# Sensors.net
KiCad netlist of a schematic drawn in Altium Designer
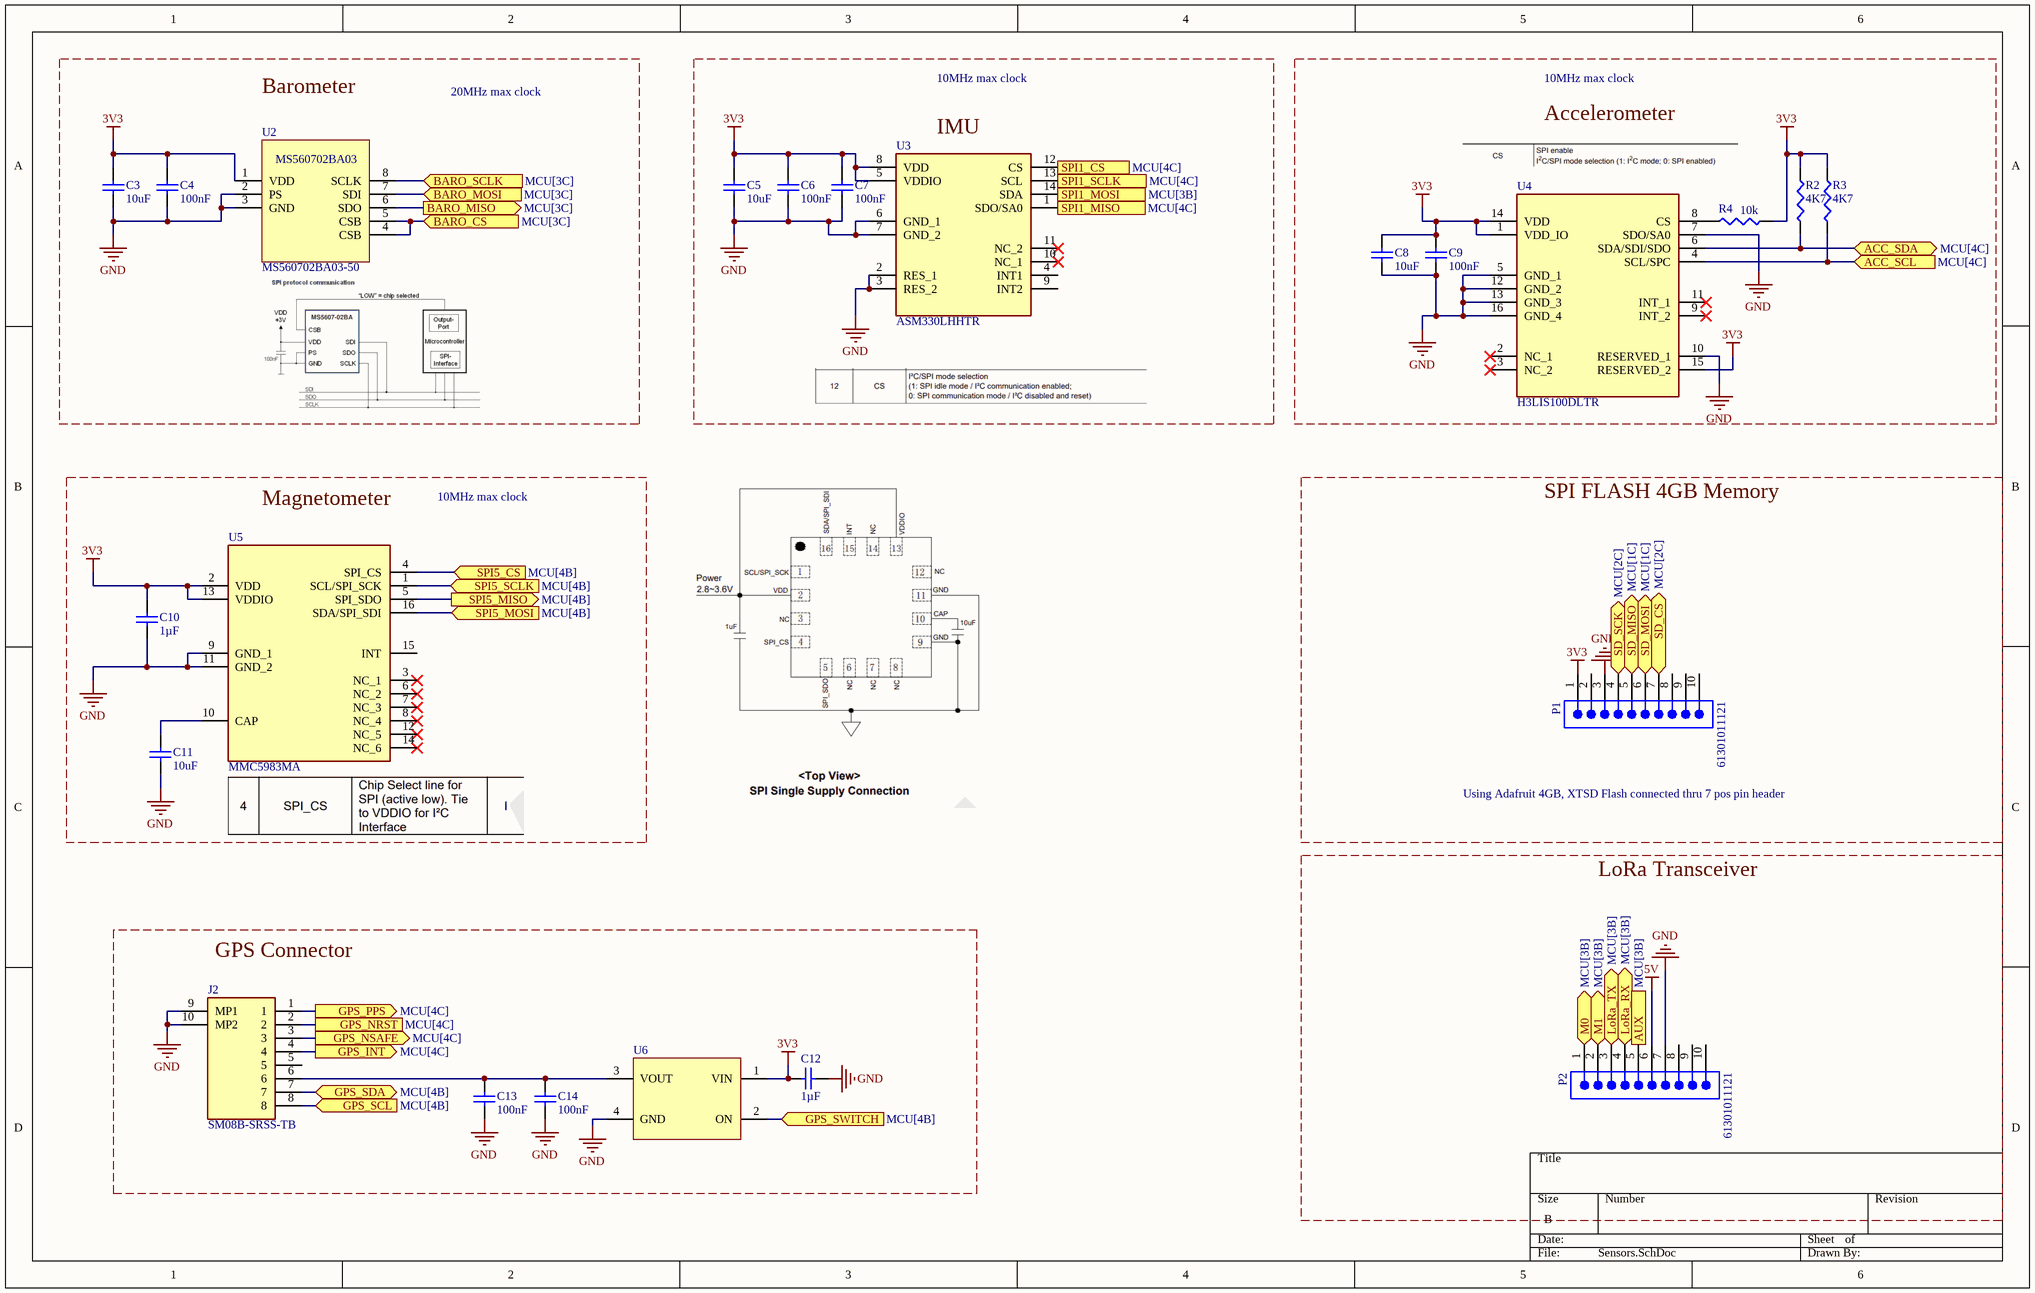
[diagram p0: Sensors.SchDoc]

(export (version "E")
  (design (tool "Eeschema 10.0.6"))
  (components
    (comp (ref "C3")
      (value "10uF")
      (footprint "0402_C")
      (fields
        (field (name "LCSC PART #") "C315248")
        (field (name "MANUFACTURER") "Samsung Electro-Mechanics")
        (field (name "MANUFACTURER PART NUMBER") "CL05A106MP5NUNC")
      )
      (libsource (lib "Flight_Computer1") (part "C_10uF_0402"))
    )
    (comp (ref "C4")
      (value "100nF")
      (footprint "0402_C")
      (fields
        (field (name "MANUFACTURER") "Samsung Electro-Mechanics")
        (field (name "MANUFACTURER PART NUMBER") "CL05B104KO5NNNC")
        (field (name "TOLERANCE") "10%")
      )
      (libsource (lib "Flight_Computer1") (part "C_100nF_0402"))
    )
    (comp (ref "C5")
      (value "10uF")
      (footprint "0402_C")
      (fields
        (field (name "LCSC PART #") "C315248")
        (field (name "MANUFACTURER") "Samsung Electro-Mechanics")
        (field (name "MANUFACTURER PART NUMBER") "CL05A106MP5NUNC")
      )
      (libsource (lib "Flight_Computer1") (part "C_10uF_0402"))
    )
    (comp (ref "C6")
      (value "100nF")
      (footprint "0402_C")
      (fields
        (field (name "MANUFACTURER") "Samsung Electro-Mechanics")
        (field (name "MANUFACTURER PART NUMBER") "CL05B104KO5NNNC")
        (field (name "TOLERANCE") "10%")
      )
      (libsource (lib "Flight_Computer1") (part "C_100nF_0402"))
    )
    (comp (ref "C7")
      (value "100nF")
      (footprint "0402_C")
      (fields
        (field (name "MANUFACTURER") "Samsung Electro-Mechanics")
        (field (name "MANUFACTURER PART NUMBER") "CL05B104KO5NNNC")
        (field (name "TOLERANCE") "10%")
      )
      (libsource (lib "Flight_Computer1") (part "C_100nF_0402"))
    )
    (comp (ref "C8")
      (value "10uF")
      (footprint "0402_C")
      (fields
        (field (name "LCSC PART #") "C315248")
        (field (name "MANUFACTURER") "Samsung Electro-Mechanics")
        (field (name "MANUFACTURER PART NUMBER") "CL05A106MP5NUNC")
      )
      (libsource (lib "Flight_Computer1") (part "C_10uF_0402"))
    )
    (comp (ref "C9")
      (value "100nF")
      (footprint "0402_C")
      (fields
        (field (name "MANUFACTURER") "Samsung Electro-Mechanics")
        (field (name "MANUFACTURER PART NUMBER") "CL05B104KO5NNNC")
        (field (name "TOLERANCE") "10%")
      )
      (libsource (lib "Flight_Computer1") (part "C_100nF_0402"))
    )
    (comp (ref "C10")
      (value "1µF")
      (footprint "0402_C")
      (fields
        (field (name "TOLERANCE") "1%")
        (field (name "POWER") "62.5mW")
        (field (name "LCSC PART NUMBER") "C307413")
        (field (name "SOURCE") "Hybrids_Avionics.SCHLIB")
      )
      (libsource (lib "Americas - Purdue University - Purdue Space Program Hybrids") (part "UMK105B7104KV-FR"))
    )
    (comp (ref "C11")
      (value "10uF")
      (footprint "0402_C")
      (fields
        (field (name "LCSC PART #") "C315248")
        (field (name "MANUFACTURER") "Samsung Electro-Mechanics")
        (field (name "MANUFACTURER PART NUMBER") "CL05A106MP5NUNC")
      )
      (libsource (lib "Flight_Computer1") (part "C_10uF_0402"))
    )
    (comp (ref "C12")
      (value "1µF")
      (footprint "0402_C")
      (fields
        (field (name "TOLERANCE") "1%")
        (field (name "POWER") "62.5mW")
        (field (name "LCSC PART NUMBER") "C307413")
        (field (name "SOURCE") "Hybrids_Avionics.SCHLIB")
      )
      (libsource (lib "Americas - Purdue University - Purdue Space Program Hybrids") (part "UMK105B7104KV-FR"))
    )
    (comp (ref "C13")
      (value "100nF")
      (footprint "0402_C")
      (fields
        (field (name "MANUFACTURER") "Samsung Electro-Mechanics")
        (field (name "MANUFACTURER PART NUMBER") "CL05B104KO5NNNC")
        (field (name "TOLERANCE") "10%")
      )
      (libsource (lib "Flight_Computer1") (part "C_100nF_0402"))
    )
    (comp (ref "C14")
      (value "100nF")
      (footprint "0402_C")
      (fields
        (field (name "MANUFACTURER") "Samsung Electro-Mechanics")
        (field (name "MANUFACTURER PART NUMBER") "CL05B104KO5NNNC")
        (field (name "TOLERANCE") "10%")
      )
      (libsource (lib "Flight_Computer1") (part "C_100nF_0402"))
    )
    (comp (ref "J2")
      (value "SM08B-SRSS-TB")
      (footprint "SM08BSRSSTBLFSN")
      (description "CONN HEADER SMD R/A 8POS 1MM")
      (fields
        (field (name "MANUFACTURER_PART_NUMBER") "SM08B-SRSS-TB(LF)(SN)")
        (field (name "MANUFACTURER") "JST")
      )
      (libsource (lib "Flight_Computer1") (part "SM08B-SRSS-TB_LF__SN_"))
    )
    (comp (ref "P1")
      (value "61301011121")
      (footprint "61301011121")
      (description "THT Vertical Pin Header WR-PHD, Pitch 2.54 mm, Single Row, 10 pins")
      (libsource (lib "Altium Content Vault") (part "Header_Male_1R_10P"))
    )
    (comp (ref "P2")
      (value "61301011121")
      (footprint "61301011121")
      (description "THT Vertical Pin Header WR-PHD, Pitch 2.54 mm, Single Row, 10 pins")
      (libsource (lib "Altium Content Vault") (part "Header_Male_1R_10P"))
    )
    (comp (ref "R2")
      (value "4K7")
      (footprint "0402_R")
      (description "RES 4.7K OHM 1% 1/16W 0402")
      (fields
        (field (name "MANUFACTURER") "TE Connectivity")
        (field (name "MANUFACTURER PART NUMBER") "CRGCQ0402F4K7")
      )
      (libsource (lib "Flight_Computer1") (part "R_4K7_0402_1"))
    )
    (comp (ref "R3")
      (value "4K7")
      (footprint "0402_R")
      (description "RES 4.7K OHM 1% 1/16W 0402")
      (fields
        (field (name "MANUFACTURER") "TE Connectivity")
        (field (name "MANUFACTURER PART NUMBER") "CRGCQ0402F4K7")
      )
      (libsource (lib "Flight_Computer1") (part "R_4K7_0402_1"))
    )
    (comp (ref "R4")
      (value "10k")
      (footprint "0402_R")
      (description "RES SMD 10K OHM 0.1% 1/16W 0402")
      (fields (field (name "LCSC PART #") "C191915") (field (name "MANUFACTURER") "Yageo Group"))
      (libsource (lib "Flight_Computer1") (part "R_10k_0402"))
    )
    (comp (ref "U2")
      (value "MS560702BA03-50")
      (footprint "MS5607-02BA03")
      (description "SENSOR 17.4PSIA 24BIT 8SMD")
      (fields (field (name "MANUFACTURER") "TE Connectivity") (field (name "LCSC PART #") "C97627"))
      (libsource (lib "Flight_Computer1") (part "MS560702BA03-50"))
    )
    (comp (ref "U3")
      (value "ASM330LHHTR")
      (footprint "LSM6DS3USTR")
      (description "Accelerometer and Gyroscope 6-Axis 3D Digital-I2C/Digital-SPI-OUT 14-Pin LGA T/R")
      (fields
        (field (name "MOUSER PART NUMBER") "511-ASM330LHHTR")
        (field (name "MANUFACTURER") "STMicroelectronics")
      )
      (libsource (lib "Flight_Computer1") (part "ASM330LHHTR"))
    )
    (comp (ref "U4")
      (value "H3LIS100DLTR")
      (footprint "H3LIS100DLTR")
      (description "ACCELEROMETER 100G I2C/SPI 16LGA")
      (fields
        (field (name "MOUSER PART NUMBER") "511-H3LIS100DLTR")
        (field (name "MANUFACTURER") "STMicroelectronics")
      )
      (libsource (lib "Flight_Computer1") (part "H3LIS100DLTR"))
    )
    (comp (ref "U5")
      (value "MMC5983MA")
      (footprint "MMC5983MA_MEM")
      (description "8 Gauss, High Performance 3-axis Magnetic Sensor Automotive AEC-Q100")
      (fields (field (name "MOUSER PART NUMBER") "438-MMC5983MA") (field (name "MANUFACTURER") "Memsic"))
      (libsource (lib "Flight_Computer1") (part "MMC5983MA"))
    )
    (comp (ref "U6")
      (value "TPS22991BNRAAR")
      (footprint "TPS22991BNRAAR-Footprint-1")
      (description "5V, 3A, 25M LOAD SWITCH WITH OPT")
      (libsource (lib "Americas - Purdue University - Purdue Space Program Hybrids") (part "TPS22991BNRAAR-Symbol-1"))
    )
  )
  (nets
    (net (code "1") (name "/ACC_SCL") (class "Default")
      (node (ref "R3") (pin "1") (pinfunction "1_1") (pintype "passive"))
      (node (ref "U4") (pin "4") (pinfunction "SCL/SPC_4") (pintype "passive"))
    )
    (net (code "2") (name "/ACC_SDA") (class "Default")
      (node (ref "R2") (pin "1") (pinfunction "1_1") (pintype "passive"))
      (node (ref "U4") (pin "6") (pinfunction "SDA/SDI/SDO_6") (pintype "passive"))
    )
    (net (code "3") (name "/AUX") (class "Default")
      (node (ref "P2") (pin "5") (pinfunction "5_5") (pintype "passive"))
    )
    (net (code "4") (name "/BARO_CS") (class "Default")
      (node (ref "U2") (pin "4") (pinfunction "CSB_4") (pintype "passive"))
      (node (ref "U2") (pin "5") (pinfunction "CSB_5") (pintype "passive"))
    )
    (net (code "5") (name "/BARO_MISO") (class "Default")
      (node (ref "U2") (pin "6") (pinfunction "SDO_6") (pintype "passive"))
    )
    (net (code "6") (name "/BARO_MOSI") (class "Default")
      (node (ref "U2") (pin "7") (pinfunction "SDI_7") (pintype "passive"))
    )
    (net (code "7") (name "/BARO_SCLK") (class "Default")
      (node (ref "U2") (pin "8") (pinfunction "SCLK_8") (pintype "passive"))
    )
    (net (code "8") (name "/GPS_INT") (class "Default")
      (node (ref "J2") (pin "4") (pinfunction "4_4") (pintype "passive"))
    )
    (net (code "9") (name "/GPS_NRST") (class "Default")
      (node (ref "J2") (pin "2") (pinfunction "2_2") (pintype "passive"))
    )
    (net (code "10") (name "/GPS_NSAFE") (class "Default")
      (node (ref "J2") (pin "3") (pinfunction "3_3") (pintype "passive"))
    )
    (net (code "11") (name "/GPS_PPS") (class "Default")
      (node (ref "J2") (pin "1") (pinfunction "1_1") (pintype "passive"))
    )
    (net (code "12") (name "/GPS_SCL") (class "Default")
      (node (ref "J2") (pin "8") (pinfunction "8_8") (pintype "passive"))
    )
    (net (code "13") (name "/GPS_SDA") (class "Default")
      (node (ref "J2") (pin "7") (pinfunction "7_7") (pintype "passive"))
    )
    (net (code "14") (name "/GPS_SWITCH") (class "Default")
      (node (ref "U6") (pin "2") (pinfunction "ON_2") (pintype "passive"))
    )
    (net (code "15") (name "/LoRa_RX") (class "Default")
      (node (ref "P2") (pin "4") (pinfunction "4_4") (pintype "passive"))
    )
    (net (code "16") (name "/LoRa_TX") (class "Default")
      (node (ref "P2") (pin "3") (pinfunction "3_3") (pintype "passive"))
    )
    (net (code "17") (name "/M0") (class "Default")
      (node (ref "P2") (pin "1") (pinfunction "1_1") (pintype "passive"))
    )
    (net (code "18") (name "/M1") (class "Default")
      (node (ref "P2") (pin "2") (pinfunction "2_2") (pintype "passive"))
    )
    (net (code "19") (name "/SD_CS") (class "Default")
      (node (ref "P1") (pin "7") (pinfunction "7_7") (pintype "passive"))
    )
    (net (code "20") (name "/SD_MISO") (class "Default")
      (node (ref "P1") (pin "5") (pinfunction "5_5") (pintype "passive"))
    )
    (net (code "21") (name "/SD_MOSI") (class "Default")
      (node (ref "P1") (pin "6") (pinfunction "6_6") (pintype "passive"))
    )
    (net (code "22") (name "/SD_SCK") (class "Default")
      (node (ref "P1") (pin "4") (pinfunction "4_4") (pintype "passive"))
    )
    (net (code "23") (name "/SPI1_CS") (class "Default")
      (node (ref "U3") (pin "12") (pinfunction "CS_12") (pintype "passive"))
    )
    (net (code "24") (name "/SPI1_MISO") (class "Default")
      (node (ref "U3") (pin "1") (pinfunction "SDO/SA0_1") (pintype "passive"))
    )
    (net (code "25") (name "/SPI1_MOSI") (class "Default")
      (node (ref "U3") (pin "14") (pinfunction "SDA_14") (pintype "passive"))
    )
    (net (code "26") (name "/SPI1_SCLK") (class "Default")
      (node (ref "U3") (pin "13") (pinfunction "SCL_13") (pintype "passive"))
    )
    (net (code "27") (name "/SPI5_CS") (class "Default")
      (node (ref "U5") (pin "4") (pinfunction "SPI_CS_4") (pintype "passive"))
    )
    (net (code "28") (name "/SPI5_MISO") (class "Default")
      (node (ref "U5") (pin "5") (pinfunction "SPI_SDO_5") (pintype "passive"))
    )
    (net (code "29") (name "/SPI5_MOSI") (class "Default")
      (node (ref "U5") (pin "16") (pinfunction "SDA/SPI_SDI_16") (pintype "passive"))
    )
    (net (code "30") (name "/SPI5_SCLK") (class "Default")
      (node (ref "U5") (pin "1") (pinfunction "SCL/SPI_SCK_1") (pintype "passive"))
    )
    (net (code "31") (name "3V3") (class "Default")
      (node (ref "C10") (pin "2") (pinfunction "2_2") (pintype "passive"))
      (node (ref "C12") (pin "2") (pinfunction "2_2") (pintype "passive"))
      (node (ref "C3") (pin "2") (pinfunction "2_2") (pintype "passive"))
      (node (ref "C4") (pin "2") (pinfunction "2_2") (pintype "passive"))
      (node (ref "C5") (pin "2") (pinfunction "2_2") (pintype "passive"))
      (node (ref "C6") (pin "2") (pinfunction "2_2") (pintype "passive"))
      (node (ref "C7") (pin "2") (pinfunction "2_2") (pintype "passive"))
      (node (ref "C8") (pin "2") (pinfunction "2_2") (pintype "passive"))
      (node (ref "C9") (pin "2") (pinfunction "2_2") (pintype "passive"))
      (node (ref "P1") (pin "1") (pinfunction "1_1") (pintype "passive"))
      (node (ref "R2") (pin "2") (pinfunction "2_2") (pintype "passive"))
      (node (ref "R3") (pin "2") (pinfunction "2_2") (pintype "passive"))
      (node (ref "R4") (pin "2") (pinfunction "2_2") (pintype "passive"))
      (node (ref "U2") (pin "1") (pinfunction "VDD_1") (pintype "passive"))
      (node (ref "U3") (pin "5") (pinfunction "VDDIO_5") (pintype "passive"))
      (node (ref "U3") (pin "8") (pinfunction "VDD_8") (pintype "passive"))
      (node (ref "U4") (pin "1") (pinfunction "VDD_IO_1") (pintype "passive"))
      (node (ref "U4") (pin "14") (pinfunction "VDD_14") (pintype "passive"))
      (node (ref "U4") (pin "15") (pinfunction "RESERVED_2_15") (pintype "passive"))
      (node (ref "U5") (pin "13") (pinfunction "VDDIO_13") (pintype "passive"))
      (node (ref "U5") (pin "2") (pinfunction "VDD_2") (pintype "passive"))
      (node (ref "U6") (pin "1") (pinfunction "VIN_1") (pintype "passive"))
    )
    (net (code "32") (name "5V") (class "Default")
      (node (ref "P2") (pin "6") (pinfunction "6_6") (pintype "passive"))
    )
    (net (code "33") (name "GND") (class "Default")
      (node (ref "C10") (pin "1") (pinfunction "1_1") (pintype "passive"))
      (node (ref "C11") (pin "1") (pinfunction "1_1") (pintype "passive"))
      (node (ref "C12") (pin "1") (pinfunction "1_1") (pintype "passive"))
      (node (ref "C13") (pin "1") (pinfunction "1_1") (pintype "passive"))
      (node (ref "C14") (pin "1") (pinfunction "1_1") (pintype "passive"))
      (node (ref "C3") (pin "1") (pinfunction "1_1") (pintype "passive"))
      (node (ref "C4") (pin "1") (pinfunction "1_1") (pintype "passive"))
      (node (ref "C5") (pin "1") (pinfunction "1_1") (pintype "passive"))
      (node (ref "C6") (pin "1") (pinfunction "1_1") (pintype "passive"))
      (node (ref "C7") (pin "1") (pinfunction "1_1") (pintype "passive"))
      (node (ref "C8") (pin "1") (pinfunction "1_1") (pintype "passive"))
      (node (ref "C9") (pin "1") (pinfunction "1_1") (pintype "passive"))
      (node (ref "J2") (pin "10") (pinfunction "MP2_10") (pintype "passive"))
      (node (ref "J2") (pin "9") (pinfunction "MP1_9") (pintype "passive"))
      (node (ref "P1") (pin "3") (pinfunction "3_3") (pintype "passive"))
      (node (ref "P2") (pin "7") (pinfunction "7_7") (pintype "passive"))
      (node (ref "U2") (pin "2") (pinfunction "PS_2") (pintype "passive"))
      (node (ref "U2") (pin "3") (pinfunction "GND_3") (pintype "passive"))
      (node (ref "U3") (pin "2") (pinfunction "RES_1_2") (pintype "passive"))
      (node (ref "U3") (pin "3") (pinfunction "RES_2_3") (pintype "passive"))
      (node (ref "U3") (pin "6") (pinfunction "GND_1_6") (pintype "passive"))
      (node (ref "U3") (pin "7") (pinfunction "GND_2_7") (pintype "passive"))
      (node (ref "U4") (pin "10") (pinfunction "RESERVED_1_10") (pintype "passive"))
      (node (ref "U4") (pin "12") (pinfunction "GND_2_12") (pintype "passive"))
      (node (ref "U4") (pin "13") (pinfunction "GND_3_13") (pintype "passive"))
      (node (ref "U4") (pin "16") (pinfunction "GND_4_16") (pintype "passive"))
      (node (ref "U4") (pin "5") (pinfunction "GND_1_5") (pintype "passive"))
      (node (ref "U4") (pin "7") (pinfunction "SDO/SA0_7") (pintype "passive"))
      (node (ref "U5") (pin "11") (pinfunction "GND_2_11") (pintype "passive"))
      (node (ref "U5") (pin "9") (pinfunction "GND_1_9") (pintype "passive"))
      (node (ref "U6") (pin "4") (pinfunction "GND_4") (pintype "passive"))
    )
    (net (code "34") (name "Net-(U4-CS)") (class "Default")
      (node (ref "R4") (pin "1") (pinfunction "1_1") (pintype "passive"))
      (node (ref "U4") (pin "8") (pinfunction "CS_8") (pintype "passive"))
    )
    (net (code "35") (name "Net-(U5-CAP)") (class "Default")
      (node (ref "C11") (pin "2") (pinfunction "2_2") (pintype "passive"))
      (node (ref "U5") (pin "10") (pinfunction "CAP_10") (pintype "passive"))
    )
    (net (code "36") (name "Net-(U6-VOUT)") (class "Default")
      (node (ref "C13") (pin "2") (pinfunction "2_2") (pintype "passive"))
      (node (ref "C14") (pin "2") (pinfunction "2_2") (pintype "passive"))
      (node (ref "J2") (pin "6") (pinfunction "6_6") (pintype "passive"))
      (node (ref "U6") (pin "3") (pinfunction "VOUT_3") (pintype "passive"))
    )
    (net (code "37") (name "unconnected-(J2-Pad5)") (class "Default")
      (node (ref "J2") (pin "5") (pinfunction "5_5") (pintype "passive"))
    )
    (net (code "38") (name "unconnected-(P1-Pad2)") (class "Default")
      (node (ref "P1") (pin "2") (pinfunction "2_2") (pintype "passive"))
    )
    (net (code "39") (name "unconnected-(P1-Pad8)") (class "Default")
      (node (ref "P1") (pin "8") (pinfunction "8_8") (pintype "passive"))
    )
    (net (code "40") (name "unconnected-(P1-Pad9)") (class "Default")
      (node (ref "P1") (pin "9") (pinfunction "9_9") (pintype "passive"))
    )
    (net (code "41") (name "unconnected-(P1-Pad10)") (class "Default")
      (node (ref "P1") (pin "10") (pinfunction "10_10") (pintype "passive"))
    )
    (net (code "42") (name "unconnected-(P2-Pad8)") (class "Default")
      (node (ref "P2") (pin "8") (pinfunction "8_8") (pintype "passive"))
    )
    (net (code "43") (name "unconnected-(P2-Pad9)") (class "Default")
      (node (ref "P2") (pin "9") (pinfunction "9_9") (pintype "passive"))
    )
    (net (code "44") (name "unconnected-(P2-Pad10)") (class "Default")
      (node (ref "P2") (pin "10") (pinfunction "10_10") (pintype "passive"))
    )
    (net (code "45") (name "unconnected-(U3-INT1-Pad4)") (class "Default")
      (node (ref "U3") (pin "4") (pinfunction "INT1_4") (pintype "passive"))
    )
    (net (code "46") (name "unconnected-(U3-INT2-Pad9)") (class "Default")
      (node (ref "U3") (pin "9") (pinfunction "INT2_9") (pintype "passive"))
    )
    (net (code "47") (name "unconnected-(U3-NC_1-Pad10)") (class "Default")
      (node (ref "U3") (pin "10") (pinfunction "NC_1_10") (pintype "passive+no_connect"))
    )
    (net (code "48") (name "unconnected-(U3-NC_2-Pad11)") (class "Default")
      (node (ref "U3") (pin "11") (pinfunction "NC_2_11") (pintype "passive+no_connect"))
    )
    (net (code "49") (name "unconnected-(U4-INT_1-Pad11)") (class "Default")
      (node (ref "U4") (pin "11") (pinfunction "INT_1_11") (pintype "passive+no_connect"))
    )
    (net (code "50") (name "unconnected-(U4-INT_2-Pad9)") (class "Default")
      (node (ref "U4") (pin "9") (pinfunction "INT_2_9") (pintype "passive+no_connect"))
    )
    (net (code "51") (name "unconnected-(U4-NC_1-Pad2)") (class "Default")
      (node (ref "U4") (pin "2") (pinfunction "NC_1_2") (pintype "passive+no_connect"))
    )
    (net (code "52") (name "unconnected-(U4-NC_2-Pad3)") (class "Default")
      (node (ref "U4") (pin "3") (pinfunction "NC_2_3") (pintype "passive+no_connect"))
    )
    (net (code "53") (name "unconnected-(U5-INT-Pad15)") (class "Default")
      (node (ref "U5") (pin "15") (pinfunction "INT_15") (pintype "passive"))
    )
    (net (code "54") (name "unconnected-(U5-NC_1-Pad3)") (class "Default")
      (node (ref "U5") (pin "3") (pinfunction "NC_1_3") (pintype "passive+no_connect"))
    )
    (net (code "55") (name "unconnected-(U5-NC_2-Pad6)") (class "Default")
      (node (ref "U5") (pin "6") (pinfunction "NC_2_6") (pintype "passive+no_connect"))
    )
    (net (code "56") (name "unconnected-(U5-NC_3-Pad7)") (class "Default")
      (node (ref "U5") (pin "7") (pinfunction "NC_3_7") (pintype "passive+no_connect"))
    )
    (net (code "57") (name "unconnected-(U5-NC_4-Pad8)") (class "Default")
      (node (ref "U5") (pin "8") (pinfunction "NC_4_8") (pintype "passive+no_connect"))
    )
    (net (code "58") (name "unconnected-(U5-NC_5-Pad12)") (class "Default")
      (node (ref "U5") (pin "12") (pinfunction "NC_5_12") (pintype "passive+no_connect"))
    )
    (net (code "59") (name "unconnected-(U5-NC_6-Pad14)") (class "Default")
      (node (ref "U5") (pin "14") (pinfunction "NC_6_14") (pintype "passive+no_connect"))
    )
  )
)
